# SH3-CONTROLS.net
KiCad netlist of a schematic drawn in Altium Designer
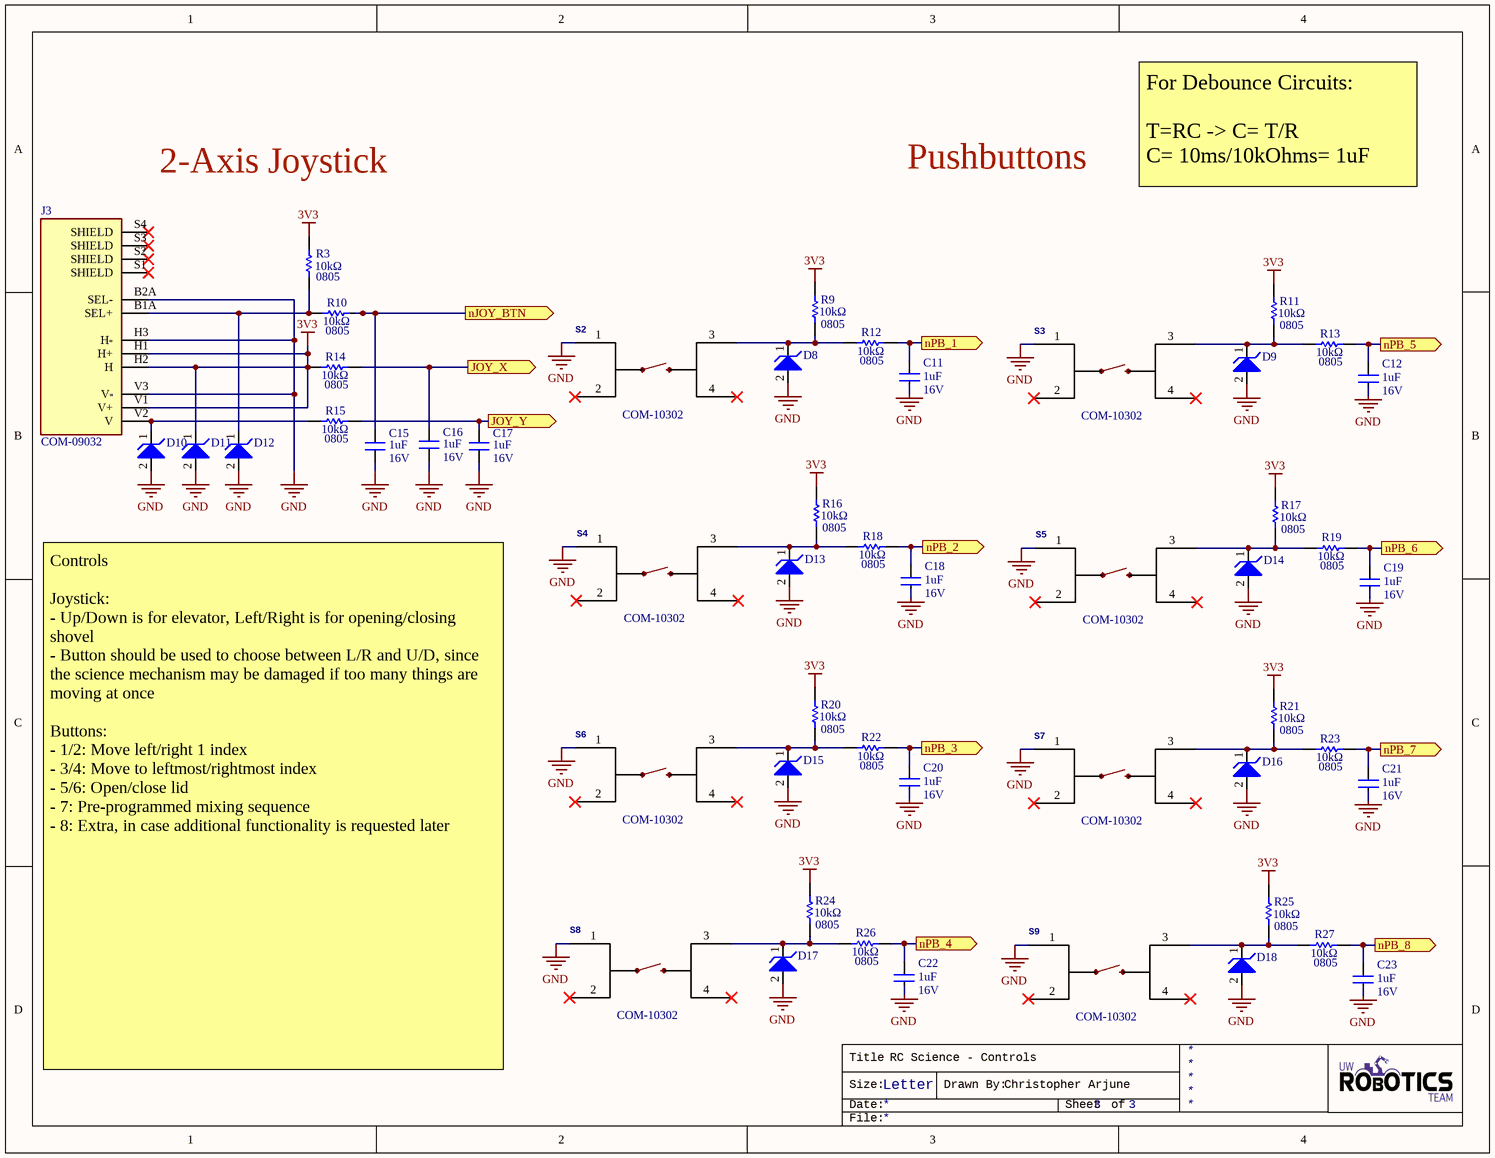
[diagram p0: SH3-CONTROLS.SchDoc]

(export (version "E")
  (design (tool "Eeschema 10.0.6"))
  (components
    (comp (ref "C11")
      (value "1uF")
      (footprint "CAPC2012X140N")
      (description "CAP CER 1UF 16V X7R 0805")
      (fields
        (field (name "TOLERANCE") "10%")
        (field (name "VOLTAGE RATING") "16V")
        (field (name "Comment") "CAP_1uF_16V_0805")
      )
      (libsource (lib "UWRT_Schematic_Library_2020") (part "CAP_1uF_16V_0805"))
    )
    (comp (ref "C12")
      (value "1uF")
      (footprint "CAPC2012X140N")
      (description "CAP CER 1UF 16V X7R 0805")
      (fields
        (field (name "TOLERANCE") "10%")
        (field (name "VOLTAGE RATING") "16V")
        (field (name "Comment") "CAP_1uF_16V_0805")
      )
      (libsource (lib "UWRT_Schematic_Library_2020") (part "CAP_1uF_16V_0805"))
    )
    (comp (ref "C15")
      (value "1uF")
      (footprint "CAPC2012X140N")
      (description "CAP CER 1UF 16V X7R 0805")
      (fields
        (field (name "TOLERANCE") "10%")
        (field (name "VOLTAGE RATING") "16V")
        (field (name "Comment") "CAP_1uF_16V_0805")
      )
      (libsource (lib "UWRT_Schematic_Library_2020") (part "CAP_1uF_16V_0805"))
    )
    (comp (ref "C16")
      (value "1uF")
      (footprint "CAPC2012X140N")
      (description "CAP CER 1UF 16V X7R 0805")
      (fields
        (field (name "TOLERANCE") "10%")
        (field (name "VOLTAGE RATING") "16V")
        (field (name "Comment") "CAP_1uF_16V_0805")
      )
      (libsource (lib "UWRT_Schematic_Library_2020") (part "CAP_1uF_16V_0805"))
    )
    (comp (ref "C17")
      (value "1uF")
      (footprint "CAPC2012X140N")
      (description "CAP CER 1UF 16V X7R 0805")
      (fields
        (field (name "TOLERANCE") "10%")
        (field (name "VOLTAGE RATING") "16V")
        (field (name "Comment") "CAP_1uF_16V_0805")
      )
      (libsource (lib "UWRT_Schematic_Library_2020") (part "CAP_1uF_16V_0805"))
    )
    (comp (ref "C18")
      (value "1uF")
      (footprint "CAPC2012X140N")
      (description "CAP CER 1UF 16V X7R 0805")
      (fields
        (field (name "TOLERANCE") "10%")
        (field (name "VOLTAGE RATING") "16V")
        (field (name "Comment") "CAP_1uF_16V_0805")
      )
      (libsource (lib "UWRT_Schematic_Library_2020") (part "CAP_1uF_16V_0805"))
    )
    (comp (ref "C19")
      (value "1uF")
      (footprint "CAPC2012X140N")
      (description "CAP CER 1UF 16V X7R 0805")
      (fields
        (field (name "TOLERANCE") "10%")
        (field (name "VOLTAGE RATING") "16V")
        (field (name "Comment") "CAP_1uF_16V_0805")
      )
      (libsource (lib "UWRT_Schematic_Library_2020") (part "CAP_1uF_16V_0805"))
    )
    (comp (ref "C20")
      (value "1uF")
      (footprint "CAPC2012X140N")
      (description "CAP CER 1UF 16V X7R 0805")
      (fields
        (field (name "TOLERANCE") "10%")
        (field (name "VOLTAGE RATING") "16V")
        (field (name "Comment") "CAP_1uF_16V_0805")
      )
      (libsource (lib "UWRT_Schematic_Library_2020") (part "CAP_1uF_16V_0805"))
    )
    (comp (ref "C21")
      (value "1uF")
      (footprint "CAPC2012X140N")
      (description "CAP CER 1UF 16V X7R 0805")
      (fields
        (field (name "TOLERANCE") "10%")
        (field (name "VOLTAGE RATING") "16V")
        (field (name "Comment") "CAP_1uF_16V_0805")
      )
      (libsource (lib "UWRT_Schematic_Library_2020") (part "CAP_1uF_16V_0805"))
    )
    (comp (ref "C22")
      (value "1uF")
      (footprint "CAPC2012X140N")
      (description "CAP CER 1UF 16V X7R 0805")
      (fields
        (field (name "TOLERANCE") "10%")
        (field (name "VOLTAGE RATING") "16V")
        (field (name "Comment") "CAP_1uF_16V_0805")
      )
      (libsource (lib "UWRT_Schematic_Library_2020") (part "CAP_1uF_16V_0805"))
    )
    (comp (ref "C23")
      (value "1uF")
      (footprint "CAPC2012X140N")
      (description "CAP CER 1UF 16V X7R 0805")
      (fields
        (field (name "TOLERANCE") "10%")
        (field (name "VOLTAGE RATING") "16V")
        (field (name "Comment") "CAP_1uF_16V_0805")
      )
      (libsource (lib "UWRT_Schematic_Library_2020") (part "CAP_1uF_16V_0805"))
    )
    (comp (ref "D8")
      (value "TVS_DIODE_UNIDIR_3.3V")
      (footprint "SOD523")
      (description "TVS DIODE 3.3V 14.1V SOD523. Used to protect each connector input line going into the MCU.")
      (libsource (lib "UWRT_Schematic_Library_2020") (part "TVS_DIODE_UNIDIR_3.3V"))
    )
    (comp (ref "D9")
      (value "TVS_DIODE_UNIDIR_3.3V")
      (footprint "SOD523")
      (description "TVS DIODE 3.3V 14.1V SOD523. Used to protect each connector input line going into the MCU.")
      (libsource (lib "UWRT_Schematic_Library_2020") (part "TVS_DIODE_UNIDIR_3.3V"))
    )
    (comp (ref "D10")
      (value "TVS_DIODE_UNIDIR_3.3V")
      (footprint "SOD523")
      (description "TVS DIODE 3.3V 14.1V SOD523. Used to protect each connector input line going into the MCU.")
      (libsource (lib "UWRT_Schematic_Library_2020") (part "TVS_DIODE_UNIDIR_3.3V"))
    )
    (comp (ref "D11")
      (value "TVS_DIODE_UNIDIR_3.3V")
      (footprint "SOD523")
      (description "TVS DIODE 3.3V 14.1V SOD523. Used to protect each connector input line going into the MCU.")
      (libsource (lib "UWRT_Schematic_Library_2020") (part "TVS_DIODE_UNIDIR_3.3V"))
    )
    (comp (ref "D12")
      (value "TVS_DIODE_UNIDIR_3.3V")
      (footprint "SOD523")
      (description "TVS DIODE 3.3V 14.1V SOD523. Used to protect each connector input line going into the MCU.")
      (libsource (lib "UWRT_Schematic_Library_2020") (part "TVS_DIODE_UNIDIR_3.3V"))
    )
    (comp (ref "D13")
      (value "TVS_DIODE_UNIDIR_3.3V")
      (footprint "SOD523")
      (description "TVS DIODE 3.3V 14.1V SOD523. Used to protect each connector input line going into the MCU.")
      (libsource (lib "UWRT_Schematic_Library_2020") (part "TVS_DIODE_UNIDIR_3.3V"))
    )
    (comp (ref "D14")
      (value "TVS_DIODE_UNIDIR_3.3V")
      (footprint "SOD523")
      (description "TVS DIODE 3.3V 14.1V SOD523. Used to protect each connector input line going into the MCU.")
      (libsource (lib "UWRT_Schematic_Library_2020") (part "TVS_DIODE_UNIDIR_3.3V"))
    )
    (comp (ref "D15")
      (value "TVS_DIODE_UNIDIR_3.3V")
      (footprint "SOD523")
      (description "TVS DIODE 3.3V 14.1V SOD523. Used to protect each connector input line going into the MCU.")
      (libsource (lib "UWRT_Schematic_Library_2020") (part "TVS_DIODE_UNIDIR_3.3V"))
    )
    (comp (ref "D16")
      (value "TVS_DIODE_UNIDIR_3.3V")
      (footprint "SOD523")
      (description "TVS DIODE 3.3V 14.1V SOD523. Used to protect each connector input line going into the MCU.")
      (libsource (lib "UWRT_Schematic_Library_2020") (part "TVS_DIODE_UNIDIR_3.3V"))
    )
    (comp (ref "D17")
      (value "TVS_DIODE_UNIDIR_3.3V")
      (footprint "SOD523")
      (description "TVS DIODE 3.3V 14.1V SOD523. Used to protect each connector input line going into the MCU.")
      (libsource (lib "UWRT_Schematic_Library_2020") (part "TVS_DIODE_UNIDIR_3.3V"))
    )
    (comp (ref "D18")
      (value "TVS_DIODE_UNIDIR_3.3V")
      (footprint "SOD523")
      (description "TVS DIODE 3.3V 14.1V SOD523. Used to protect each connector input line going into the MCU.")
      (libsource (lib "UWRT_Schematic_Library_2020") (part "TVS_DIODE_UNIDIR_3.3V"))
    )
    (comp (ref "J3")
      (value "2_AXIS_JOYSTICK")
      (footprint "2_AXIS_JOY")
      (description "JOYSTICK 10K OHM 2 AXIS TH")
      (fields (field (name "MANUFACTURER PART NUMBER 1") "COM-09032"))
      (libsource (lib "UWRT_Schematic_Library_2020") (part "2_AXIS_JOYSTICK"))
    )
    (comp (ref "R3")
      (value "10kΩ")
      (footprint "RESC2012X60N")
      (description "RES SMD 10K OHM 1% 1/8W 0805")
      (fields
        (field (name "TOLERANCE") "1%")
        (field (name "CASE CODE (IMPERIAL)") "0805")
        (field (name "Comment") "RES_10kΩ_0805")
      )
      (libsource (lib "UWRT_Schematic_Library_2020") (part "RES_10kΩ_0805"))
    )
    (comp (ref "R9")
      (value "10kΩ")
      (footprint "RESC2012X60N")
      (description "RES SMD 10K OHM 1% 1/8W 0805")
      (fields
        (field (name "TOLERANCE") "1%")
        (field (name "CASE CODE (IMPERIAL)") "0805")
        (field (name "Comment") "RES_10kΩ_0805")
      )
      (libsource (lib "UWRT_Schematic_Library_2020") (part "RES_10kΩ_0805"))
    )
    (comp (ref "R10")
      (value "10kΩ")
      (footprint "RESC2012X60N")
      (description "RES SMD 10K OHM 1% 1/8W 0805")
      (fields
        (field (name "CASE CODE (IMPERIAL)") "0805")
        (field (name "TOLERANCE") "1%")
        (field (name "Comment") "RES_10kΩ_0805")
      )
      (libsource (lib "UWRT_Schematic_Library_2020") (part "RES_10kΩ_0805"))
    )
    (comp (ref "R11")
      (value "10kΩ")
      (footprint "RESC2012X60N")
      (description "RES SMD 10K OHM 1% 1/8W 0805")
      (fields
        (field (name "TOLERANCE") "1%")
        (field (name "CASE CODE (IMPERIAL)") "0805")
        (field (name "Comment") "RES_10kΩ_0805")
      )
      (libsource (lib "UWRT_Schematic_Library_2020") (part "RES_10kΩ_0805"))
    )
    (comp (ref "R12")
      (value "10kΩ")
      (footprint "RESC2012X60N")
      (description "RES SMD 10K OHM 1% 1/8W 0805")
      (fields
        (field (name "CASE CODE (IMPERIAL)") "0805")
        (field (name "TOLERANCE") "1%")
        (field (name "Comment") "RES_10kΩ_0805")
      )
      (libsource (lib "UWRT_Schematic_Library_2020") (part "RES_10kΩ_0805"))
    )
    (comp (ref "R13")
      (value "10kΩ")
      (footprint "RESC2012X60N")
      (description "RES SMD 10K OHM 1% 1/8W 0805")
      (fields
        (field (name "CASE CODE (IMPERIAL)") "0805")
        (field (name "TOLERANCE") "1%")
        (field (name "Comment") "RES_10kΩ_0805")
      )
      (libsource (lib "UWRT_Schematic_Library_2020") (part "RES_10kΩ_0805"))
    )
    (comp (ref "R14")
      (value "10kΩ")
      (footprint "RESC2012X60N")
      (description "RES SMD 10K OHM 1% 1/8W 0805")
      (fields
        (field (name "CASE CODE (IMPERIAL)") "0805")
        (field (name "TOLERANCE") "1%")
        (field (name "Comment") "RES_10kΩ_0805")
      )
      (libsource (lib "UWRT_Schematic_Library_2020") (part "RES_10kΩ_0805"))
    )
    (comp (ref "R15")
      (value "10kΩ")
      (footprint "RESC2012X60N")
      (description "RES SMD 10K OHM 1% 1/8W 0805")
      (fields
        (field (name "CASE CODE (IMPERIAL)") "0805")
        (field (name "TOLERANCE") "1%")
        (field (name "Comment") "RES_10kΩ_0805")
      )
      (libsource (lib "UWRT_Schematic_Library_2020") (part "RES_10kΩ_0805"))
    )
    (comp (ref "R16")
      (value "10kΩ")
      (footprint "RESC2012X60N")
      (description "RES SMD 10K OHM 1% 1/8W 0805")
      (fields
        (field (name "TOLERANCE") "1%")
        (field (name "CASE CODE (IMPERIAL)") "0805")
        (field (name "Comment") "RES_10kΩ_0805")
      )
      (libsource (lib "UWRT_Schematic_Library_2020") (part "RES_10kΩ_0805"))
    )
    (comp (ref "R17")
      (value "10kΩ")
      (footprint "RESC2012X60N")
      (description "RES SMD 10K OHM 1% 1/8W 0805")
      (fields
        (field (name "TOLERANCE") "1%")
        (field (name "CASE CODE (IMPERIAL)") "0805")
        (field (name "Comment") "RES_10kΩ_0805")
      )
      (libsource (lib "UWRT_Schematic_Library_2020") (part "RES_10kΩ_0805"))
    )
    (comp (ref "R18")
      (value "10kΩ")
      (footprint "RESC2012X60N")
      (description "RES SMD 10K OHM 1% 1/8W 0805")
      (fields
        (field (name "CASE CODE (IMPERIAL)") "0805")
        (field (name "TOLERANCE") "1%")
        (field (name "Comment") "RES_10kΩ_0805")
      )
      (libsource (lib "UWRT_Schematic_Library_2020") (part "RES_10kΩ_0805"))
    )
    (comp (ref "R19")
      (value "10kΩ")
      (footprint "RESC2012X60N")
      (description "RES SMD 10K OHM 1% 1/8W 0805")
      (fields
        (field (name "CASE CODE (IMPERIAL)") "0805")
        (field (name "TOLERANCE") "1%")
        (field (name "Comment") "RES_10kΩ_0805")
      )
      (libsource (lib "UWRT_Schematic_Library_2020") (part "RES_10kΩ_0805"))
    )
    (comp (ref "R20")
      (value "10kΩ")
      (footprint "RESC2012X60N")
      (description "RES SMD 10K OHM 1% 1/8W 0805")
      (fields
        (field (name "TOLERANCE") "1%")
        (field (name "CASE CODE (IMPERIAL)") "0805")
        (field (name "Comment") "RES_10kΩ_0805")
      )
      (libsource (lib "UWRT_Schematic_Library_2020") (part "RES_10kΩ_0805"))
    )
    (comp (ref "R21")
      (value "10kΩ")
      (footprint "RESC2012X60N")
      (description "RES SMD 10K OHM 1% 1/8W 0805")
      (fields
        (field (name "TOLERANCE") "1%")
        (field (name "CASE CODE (IMPERIAL)") "0805")
        (field (name "Comment") "RES_10kΩ_0805")
      )
      (libsource (lib "UWRT_Schematic_Library_2020") (part "RES_10kΩ_0805"))
    )
    (comp (ref "R22")
      (value "10kΩ")
      (footprint "RESC2012X60N")
      (description "RES SMD 10K OHM 1% 1/8W 0805")
      (fields
        (field (name "CASE CODE (IMPERIAL)") "0805")
        (field (name "TOLERANCE") "1%")
        (field (name "Comment") "RES_10kΩ_0805")
      )
      (libsource (lib "UWRT_Schematic_Library_2020") (part "RES_10kΩ_0805"))
    )
    (comp (ref "R23")
      (value "10kΩ")
      (footprint "RESC2012X60N")
      (description "RES SMD 10K OHM 1% 1/8W 0805")
      (fields
        (field (name "CASE CODE (IMPERIAL)") "0805")
        (field (name "TOLERANCE") "1%")
        (field (name "Comment") "RES_10kΩ_0805")
      )
      (libsource (lib "UWRT_Schematic_Library_2020") (part "RES_10kΩ_0805"))
    )
    (comp (ref "R24")
      (value "10kΩ")
      (footprint "RESC2012X60N")
      (description "RES SMD 10K OHM 1% 1/8W 0805")
      (fields
        (field (name "TOLERANCE") "1%")
        (field (name "CASE CODE (IMPERIAL)") "0805")
        (field (name "Comment") "RES_10kΩ_0805")
      )
      (libsource (lib "UWRT_Schematic_Library_2020") (part "RES_10kΩ_0805"))
    )
    (comp (ref "R25")
      (value "10kΩ")
      (footprint "RESC2012X60N")
      (description "RES SMD 10K OHM 1% 1/8W 0805")
      (fields
        (field (name "TOLERANCE") "1%")
        (field (name "CASE CODE (IMPERIAL)") "0805")
        (field (name "Comment") "RES_10kΩ_0805")
      )
      (libsource (lib "UWRT_Schematic_Library_2020") (part "RES_10kΩ_0805"))
    )
    (comp (ref "R26")
      (value "10kΩ")
      (footprint "RESC2012X60N")
      (description "RES SMD 10K OHM 1% 1/8W 0805")
      (fields
        (field (name "CASE CODE (IMPERIAL)") "0805")
        (field (name "TOLERANCE") "1%")
        (field (name "Comment") "RES_10kΩ_0805")
      )
      (libsource (lib "UWRT_Schematic_Library_2020") (part "RES_10kΩ_0805"))
    )
    (comp (ref "R27")
      (value "10kΩ")
      (footprint "RESC2012X60N")
      (description "RES SMD 10K OHM 1% 1/8W 0805")
      (fields
        (field (name "CASE CODE (IMPERIAL)") "0805")
        (field (name "TOLERANCE") "1%")
        (field (name "Comment") "RES_10kΩ_0805")
      )
      (libsource (lib "UWRT_Schematic_Library_2020") (part "RES_10kΩ_0805"))
    )
    (comp (ref "S2")
      (value "Pushbutton")
      (footprint "TACTILE_SWITCH_PTH_12MM")
      (description "Momentary Switch (Pushbutton) - SPST")
      (fields (field (name "MANUFACTURER PART NUMBER 1") "COM-10302"))
      (libsource (lib "UWRT_Schematic_Library_2020") (part "MOMENTARY_SWITCH_TH"))
    )
    (comp (ref "S3")
      (value "Pushbutton")
      (footprint "TACTILE_SWITCH_PTH_12MM")
      (description "Momentary Switch (Pushbutton) - SPST")
      (fields (field (name "MANUFACTURER PART NUMBER 1") "COM-10302"))
      (libsource (lib "UWRT_Schematic_Library_2020") (part "MOMENTARY_SWITCH_TH"))
    )
    (comp (ref "S4")
      (value "Pushbutton")
      (footprint "TACTILE_SWITCH_PTH_12MM")
      (description "Momentary Switch (Pushbutton) - SPST")
      (fields (field (name "MANUFACTURER PART NUMBER 1") "COM-10302"))
      (libsource (lib "UWRT_Schematic_Library_2020") (part "MOMENTARY_SWITCH_TH"))
    )
    (comp (ref "S5")
      (value "Pushbutton")
      (footprint "TACTILE_SWITCH_PTH_12MM")
      (description "Momentary Switch (Pushbutton) - SPST")
      (fields (field (name "MANUFACTURER PART NUMBER 1") "COM-10302"))
      (libsource (lib "UWRT_Schematic_Library_2020") (part "MOMENTARY_SWITCH_TH"))
    )
    (comp (ref "S6")
      (value "Pushbutton")
      (footprint "TACTILE_SWITCH_PTH_12MM")
      (description "Momentary Switch (Pushbutton) - SPST")
      (fields (field (name "MANUFACTURER PART NUMBER 1") "COM-10302"))
      (libsource (lib "UWRT_Schematic_Library_2020") (part "MOMENTARY_SWITCH_TH"))
    )
    (comp (ref "S7")
      (value "Pushbutton")
      (footprint "TACTILE_SWITCH_PTH_12MM")
      (description "Momentary Switch (Pushbutton) - SPST")
      (fields (field (name "MANUFACTURER PART NUMBER 1") "COM-10302"))
      (libsource (lib "UWRT_Schematic_Library_2020") (part "MOMENTARY_SWITCH_TH"))
    )
    (comp (ref "S8")
      (value "Pushbutton")
      (footprint "TACTILE_SWITCH_PTH_12MM")
      (description "Momentary Switch (Pushbutton) - SPST")
      (fields (field (name "MANUFACTURER PART NUMBER 1") "COM-10302"))
      (libsource (lib "UWRT_Schematic_Library_2020") (part "MOMENTARY_SWITCH_TH"))
    )
    (comp (ref "S9")
      (value "Pushbutton")
      (footprint "TACTILE_SWITCH_PTH_12MM")
      (description "Momentary Switch (Pushbutton) - SPST")
      (fields (field (name "MANUFACTURER PART NUMBER 1") "COM-10302"))
      (libsource (lib "UWRT_Schematic_Library_2020") (part "MOMENTARY_SWITCH_TH"))
    )
  )
  (nets
    (net (code "1") (name "/JOY_X") (class "Default")
      (node (ref "C16") (pin "2") (pinfunction "2_2") (pintype "passive"))
      (node (ref "R14") (pin "2") (pinfunction "2_2") (pintype "passive"))
    )
    (net (code "2") (name "/JOY_Y") (class "Default")
      (node (ref "C17") (pin "2") (pinfunction "2_2") (pintype "passive"))
      (node (ref "R15") (pin "2") (pinfunction "2_2") (pintype "passive"))
    )
    (net (code "3") (name "/nJOY_BTN") (class "Default")
      (node (ref "C15") (pin "2") (pinfunction "2_2") (pintype "passive"))
      (node (ref "R10") (pin "2") (pinfunction "2_2") (pintype "passive"))
    )
    (net (code "4") (name "/nPB_1") (class "Default")
      (node (ref "C11") (pin "2") (pinfunction "2_2") (pintype "passive"))
      (node (ref "R12") (pin "2") (pinfunction "2_2") (pintype "passive"))
    )
    (net (code "5") (name "/nPB_2") (class "Default")
      (node (ref "C18") (pin "2") (pinfunction "2_2") (pintype "passive"))
      (node (ref "R18") (pin "2") (pinfunction "2_2") (pintype "passive"))
    )
    (net (code "6") (name "/nPB_3") (class "Default")
      (node (ref "C20") (pin "2") (pinfunction "2_2") (pintype "passive"))
      (node (ref "R22") (pin "2") (pinfunction "2_2") (pintype "passive"))
    )
    (net (code "7") (name "/nPB_4") (class "Default")
      (node (ref "C22") (pin "2") (pinfunction "2_2") (pintype "passive"))
      (node (ref "R26") (pin "2") (pinfunction "2_2") (pintype "passive"))
    )
    (net (code "8") (name "/nPB_5") (class "Default")
      (node (ref "C12") (pin "2") (pinfunction "2_2") (pintype "passive"))
      (node (ref "R13") (pin "2") (pinfunction "2_2") (pintype "passive"))
    )
    (net (code "9") (name "/nPB_6") (class "Default")
      (node (ref "C19") (pin "2") (pinfunction "2_2") (pintype "passive"))
      (node (ref "R19") (pin "2") (pinfunction "2_2") (pintype "passive"))
    )
    (net (code "10") (name "/nPB_7") (class "Default")
      (node (ref "C21") (pin "2") (pinfunction "2_2") (pintype "passive"))
      (node (ref "R23") (pin "2") (pinfunction "2_2") (pintype "passive"))
    )
    (net (code "11") (name "/nPB_8") (class "Default")
      (node (ref "C23") (pin "2") (pinfunction "2_2") (pintype "passive"))
      (node (ref "R27") (pin "2") (pinfunction "2_2") (pintype "passive"))
    )
    (net (code "12") (name "3V3") (class "Default")
      (node (ref "D11") (pin "1") (pinfunction "1_1") (pintype "passive"))
      (node (ref "J3") (pin "H1") (pinfunction "H+_H1") (pintype "passive"))
      (node (ref "J3") (pin "H2") (pinfunction "H_H2") (pintype "passive"))
      (node (ref "J3") (pin "V1") (pinfunction "V+_V1") (pintype "passive"))
      (node (ref "R11") (pin "1") (pinfunction "1_1") (pintype "passive"))
      (node (ref "R14") (pin "1") (pinfunction "1_1") (pintype "passive"))
      (node (ref "R16") (pin "1") (pinfunction "1_1") (pintype "passive"))
      (node (ref "R17") (pin "1") (pinfunction "1_1") (pintype "passive"))
      (node (ref "R20") (pin "1") (pinfunction "1_1") (pintype "passive"))
      (node (ref "R21") (pin "1") (pinfunction "1_1") (pintype "passive"))
      (node (ref "R24") (pin "1") (pinfunction "1_1") (pintype "passive"))
      (node (ref "R25") (pin "1") (pinfunction "1_1") (pintype "passive"))
      (node (ref "R3") (pin "1") (pinfunction "1_1") (pintype "passive"))
      (node (ref "R9") (pin "1") (pinfunction "1_1") (pintype "passive"))
    )
    (net (code "13") (name "GND") (class "Default")
      (node (ref "C11") (pin "1") (pinfunction "1_1") (pintype "passive"))
      (node (ref "C12") (pin "1") (pinfunction "1_1") (pintype "passive"))
      (node (ref "C15") (pin "1") (pinfunction "1_1") (pintype "passive"))
      (node (ref "C16") (pin "1") (pinfunction "1_1") (pintype "passive"))
      (node (ref "C17") (pin "1") (pinfunction "1_1") (pintype "passive"))
      (node (ref "C18") (pin "1") (pinfunction "1_1") (pintype "passive"))
      (node (ref "C19") (pin "1") (pinfunction "1_1") (pintype "passive"))
      (node (ref "C20") (pin "1") (pinfunction "1_1") (pintype "passive"))
      (node (ref "C21") (pin "1") (pinfunction "1_1") (pintype "passive"))
      (node (ref "C22") (pin "1") (pinfunction "1_1") (pintype "passive"))
      (node (ref "C23") (pin "1") (pinfunction "1_1") (pintype "passive"))
      (node (ref "D10") (pin "2") (pinfunction "2_2") (pintype "passive"))
      (node (ref "D11") (pin "2") (pinfunction "2_2") (pintype "passive"))
      (node (ref "D12") (pin "2") (pinfunction "2_2") (pintype "passive"))
      (node (ref "D13") (pin "2") (pinfunction "2_2") (pintype "passive"))
      (node (ref "D14") (pin "2") (pinfunction "2_2") (pintype "passive"))
      (node (ref "D15") (pin "2") (pinfunction "2_2") (pintype "passive"))
      (node (ref "D16") (pin "2") (pinfunction "2_2") (pintype "passive"))
      (node (ref "D17") (pin "2") (pinfunction "2_2") (pintype "passive"))
      (node (ref "D18") (pin "2") (pinfunction "2_2") (pintype "passive"))
      (node (ref "D8") (pin "2") (pinfunction "2_2") (pintype "passive"))
      (node (ref "D9") (pin "2") (pinfunction "2_2") (pintype "passive"))
      (node (ref "J3") (pin "B2A") (pinfunction "SEL-_B2A") (pintype "passive"))
      (node (ref "J3") (pin "H3") (pinfunction "H-_H3") (pintype "passive"))
      (node (ref "J3") (pin "V3") (pinfunction "V-_V3") (pintype "passive"))
      (node (ref "S2") (pin "1") (pinfunction "1_1") (pintype "passive"))
      (node (ref "S3") (pin "1") (pinfunction "1_1") (pintype "passive"))
      (node (ref "S4") (pin "1") (pinfunction "1_1") (pintype "passive"))
      (node (ref "S5") (pin "1") (pinfunction "1_1") (pintype "passive"))
      (node (ref "S6") (pin "1") (pinfunction "1_1") (pintype "passive"))
      (node (ref "S7") (pin "1") (pinfunction "1_1") (pintype "passive"))
      (node (ref "S8") (pin "1") (pinfunction "1_1") (pintype "passive"))
      (node (ref "S9") (pin "1") (pinfunction "1_1") (pintype "passive"))
    )
    (net (code "14") (name "Net-(D8-Pad1)") (class "Default")
      (node (ref "D8") (pin "1") (pinfunction "1_1") (pintype "passive"))
      (node (ref "R12") (pin "1") (pinfunction "1_1") (pintype "passive"))
      (node (ref "R9") (pin "2") (pinfunction "2_2") (pintype "passive"))
      (node (ref "S2") (pin "3") (pinfunction "3_3") (pintype "passive"))
    )
    (net (code "15") (name "Net-(D9-Pad1)") (class "Default")
      (node (ref "D9") (pin "1") (pinfunction "1_1") (pintype "passive"))
      (node (ref "R11") (pin "2") (pinfunction "2_2") (pintype "passive"))
      (node (ref "R13") (pin "1") (pinfunction "1_1") (pintype "passive"))
      (node (ref "S3") (pin "3") (pinfunction "3_3") (pintype "passive"))
    )
    (net (code "16") (name "Net-(D13-Pad1)") (class "Default")
      (node (ref "D13") (pin "1") (pinfunction "1_1") (pintype "passive"))
      (node (ref "R16") (pin "2") (pinfunction "2_2") (pintype "passive"))
      (node (ref "R18") (pin "1") (pinfunction "1_1") (pintype "passive"))
      (node (ref "S4") (pin "3") (pinfunction "3_3") (pintype "passive"))
    )
    (net (code "17") (name "Net-(D14-Pad1)") (class "Default")
      (node (ref "D14") (pin "1") (pinfunction "1_1") (pintype "passive"))
      (node (ref "R17") (pin "2") (pinfunction "2_2") (pintype "passive"))
      (node (ref "R19") (pin "1") (pinfunction "1_1") (pintype "passive"))
      (node (ref "S5") (pin "3") (pinfunction "3_3") (pintype "passive"))
    )
    (net (code "18") (name "Net-(D15-Pad1)") (class "Default")
      (node (ref "D15") (pin "1") (pinfunction "1_1") (pintype "passive"))
      (node (ref "R20") (pin "2") (pinfunction "2_2") (pintype "passive"))
      (node (ref "R22") (pin "1") (pinfunction "1_1") (pintype "passive"))
      (node (ref "S6") (pin "3") (pinfunction "3_3") (pintype "passive"))
    )
    (net (code "19") (name "Net-(D16-Pad1)") (class "Default")
      (node (ref "D16") (pin "1") (pinfunction "1_1") (pintype "passive"))
      (node (ref "R21") (pin "2") (pinfunction "2_2") (pintype "passive"))
      (node (ref "R23") (pin "1") (pinfunction "1_1") (pintype "passive"))
      (node (ref "S7") (pin "3") (pinfunction "3_3") (pintype "passive"))
    )
    (net (code "20") (name "Net-(D17-Pad1)") (class "Default")
      (node (ref "D17") (pin "1") (pinfunction "1_1") (pintype "passive"))
      (node (ref "R24") (pin "2") (pinfunction "2_2") (pintype "passive"))
      (node (ref "R26") (pin "1") (pinfunction "1_1") (pintype "passive"))
      (node (ref "S8") (pin "3") (pinfunction "3_3") (pintype "passive"))
    )
    (net (code "21") (name "Net-(D18-Pad1)") (class "Default")
      (node (ref "D18") (pin "1") (pinfunction "1_1") (pintype "passive"))
      (node (ref "R25") (pin "2") (pinfunction "2_2") (pintype "passive"))
      (node (ref "R27") (pin "1") (pinfunction "1_1") (pintype "passive"))
      (node (ref "S9") (pin "3") (pinfunction "3_3") (pintype "passive"))
    )
    (net (code "22") (name "Net-(J3-SEL+)") (class "Default")
      (node (ref "D12") (pin "1") (pinfunction "1_1") (pintype "passive"))
      (node (ref "J3") (pin "B1A") (pinfunction "SEL+_B1A") (pintype "passive"))
      (node (ref "R10") (pin "1") (pinfunction "1_1") (pintype "passive"))
      (node (ref "R3") (pin "2") (pinfunction "2_2") (pintype "passive"))
    )
    (net (code "23") (name "Net-(J3-V)") (class "Default")
      (node (ref "D10") (pin "1") (pinfunction "1_1") (pintype "passive"))
      (node (ref "J3") (pin "V2") (pinfunction "V_V2") (pintype "passive"))
      (node (ref "R15") (pin "1") (pinfunction "1_1") (pintype "passive"))
    )
    (net (code "24") (name "unconnected-(J3-SHIELD-PadS1)") (class "Default")
      (node (ref "J3") (pin "S1") (pinfunction "SHIELD_S1") (pintype "passive+no_connect"))
    )
    (net (code "25") (name "unconnected-(J3-SHIELD-PadS2)") (class "Default")
      (node (ref "J3") (pin "S2") (pinfunction "SHIELD_S2") (pintype "passive+no_connect"))
    )
    (net (code "26") (name "unconnected-(J3-SHIELD-PadS3)") (class "Default")
      (node (ref "J3") (pin "S3") (pinfunction "SHIELD_S3") (pintype "passive+no_connect"))
    )
    (net (code "27") (name "unconnected-(J3-SHIELD-PadS4)") (class "Default")
      (node (ref "J3") (pin "S4") (pinfunction "SHIELD_S4") (pintype "passive+no_connect"))
    )
    (net (code "28") (name "unconnected-(S2-Pad2)") (class "Default")
      (node (ref "S2") (pin "2") (pinfunction "2_2") (pintype "passive+no_connect"))
    )
    (net (code "29") (name "unconnected-(S2-Pad4)") (class "Default")
      (node (ref "S2") (pin "4") (pinfunction "4_4") (pintype "passive+no_connect"))
    )
    (net (code "30") (name "unconnected-(S3-Pad2)") (class "Default")
      (node (ref "S3") (pin "2") (pinfunction "2_2") (pintype "passive+no_connect"))
    )
    (net (code "31") (name "unconnected-(S3-Pad4)") (class "Default")
      (node (ref "S3") (pin "4") (pinfunction "4_4") (pintype "passive+no_connect"))
    )
    (net (code "32") (name "unconnected-(S4-Pad2)") (class "Default")
      (node (ref "S4") (pin "2") (pinfunction "2_2") (pintype "passive+no_connect"))
    )
    (net (code "33") (name "unconnected-(S4-Pad4)") (class "Default")
      (node (ref "S4") (pin "4") (pinfunction "4_4") (pintype "passive+no_connect"))
    )
    (net (code "34") (name "unconnected-(S5-Pad2)") (class "Default")
      (node (ref "S5") (pin "2") (pinfunction "2_2") (pintype "passive+no_connect"))
    )
    (net (code "35") (name "unconnected-(S5-Pad4)") (class "Default")
      (node (ref "S5") (pin "4") (pinfunction "4_4") (pintype "passive+no_connect"))
    )
    (net (code "36") (name "unconnected-(S6-Pad2)") (class "Default")
      (node (ref "S6") (pin "2") (pinfunction "2_2") (pintype "passive+no_connect"))
    )
    (net (code "37") (name "unconnected-(S6-Pad4)") (class "Default")
      (node (ref "S6") (pin "4") (pinfunction "4_4") (pintype "passive+no_connect"))
    )
    (net (code "38") (name "unconnected-(S7-Pad2)") (class "Default")
      (node (ref "S7") (pin "2") (pinfunction "2_2") (pintype "passive+no_connect"))
    )
    (net (code "39") (name "unconnected-(S7-Pad4)") (class "Default")
      (node (ref "S7") (pin "4") (pinfunction "4_4") (pintype "passive+no_connect"))
    )
    (net (code "40") (name "unconnected-(S8-Pad2)") (class "Default")
      (node (ref "S8") (pin "2") (pinfunction "2_2") (pintype "passive+no_connect"))
    )
    (net (code "41") (name "unconnected-(S8-Pad4)") (class "Default")
      (node (ref "S8") (pin "4") (pinfunction "4_4") (pintype "passive+no_connect"))
    )
    (net (code "42") (name "unconnected-(S9-Pad2)") (class "Default")
      (node (ref "S9") (pin "2") (pinfunction "2_2") (pintype "passive+no_connect"))
    )
    (net (code "43") (name "unconnected-(S9-Pad4)") (class "Default")
      (node (ref "S9") (pin "4") (pinfunction "4_4") (pintype "passive+no_connect"))
    )
  )
)
